# automa_o_granja.net
KiCad netlist of a schematic drawn in EAGLE
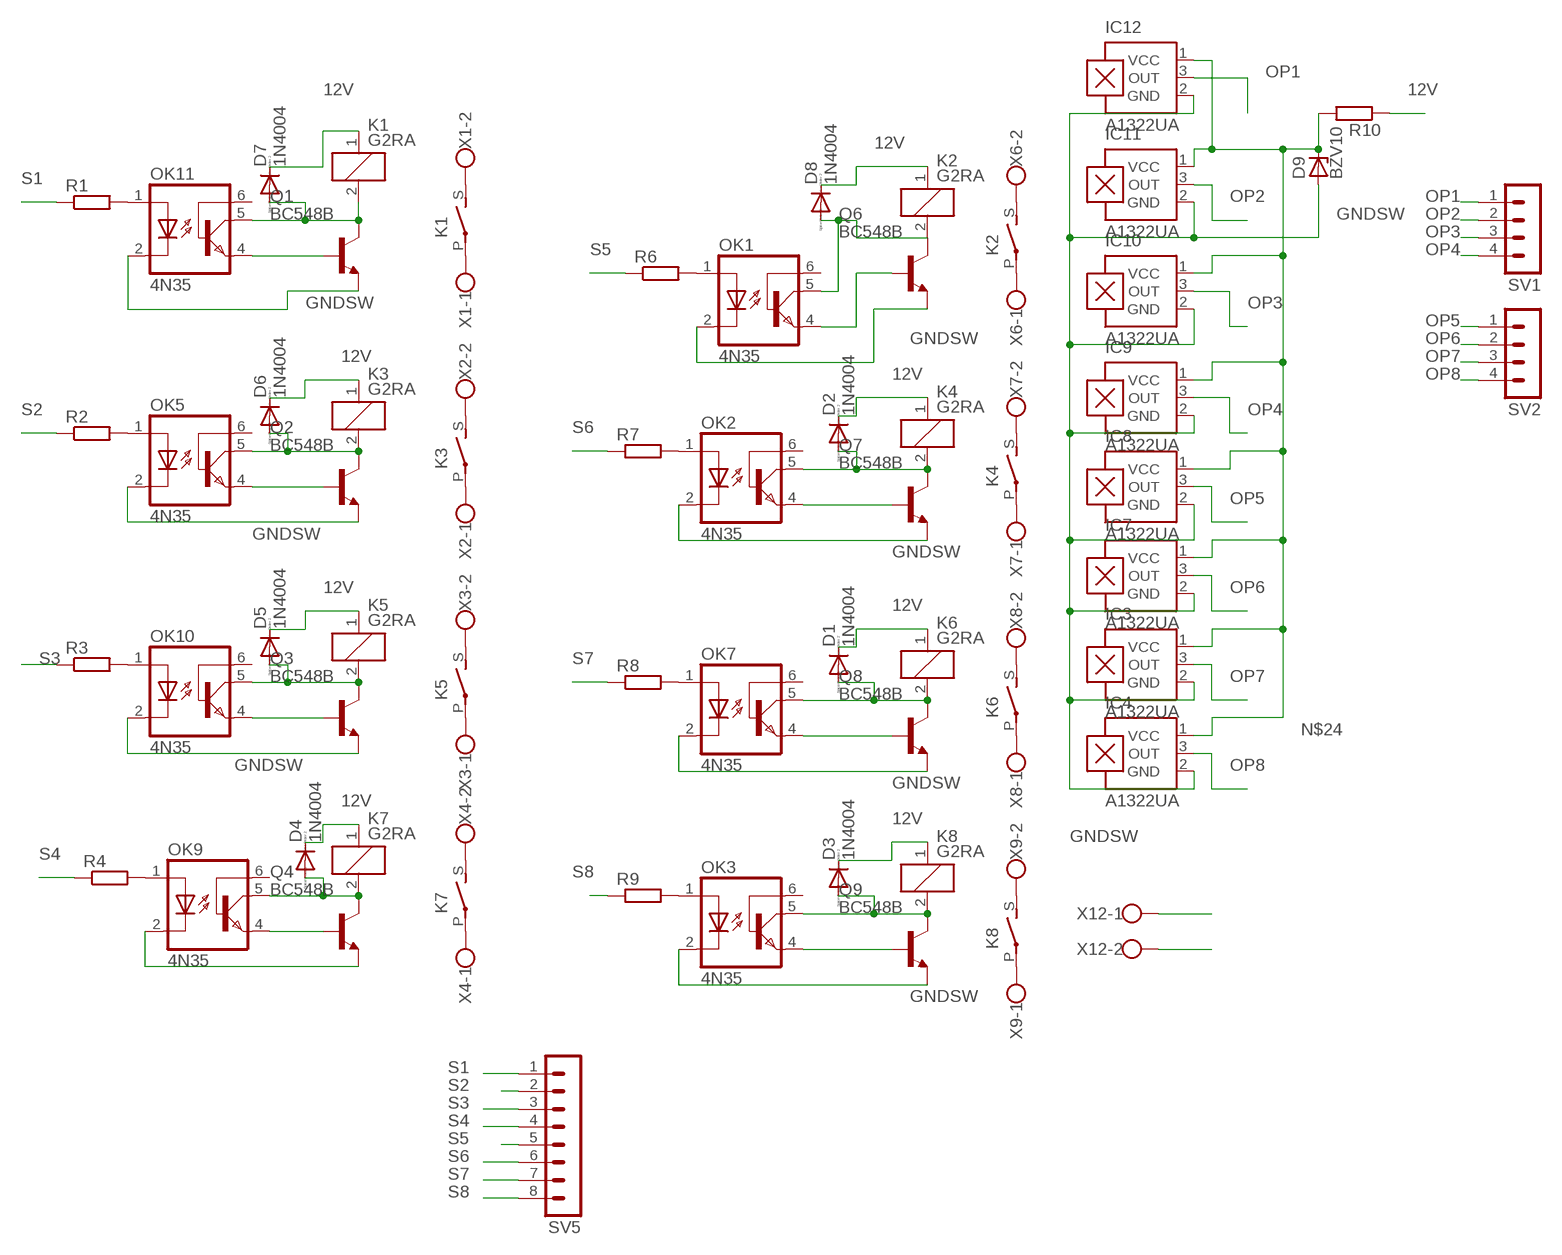
[diagram p0: schematic, sheet 1]

(export (version "E")
  (design (tool "Eeschema 10.0.6"))
  (components
    (comp (ref "D1")
      (value "1N4004")
      (footprint "eagle-import:DO41-10")
      (libsource (lib "eagle-import") (part "1N4004"))
    )
    (comp (ref "D2")
      (value "1N4004")
      (footprint "eagle-import:DO41-10")
      (libsource (lib "eagle-import") (part "1N4004"))
    )
    (comp (ref "D3")
      (value "1N4004")
      (footprint "eagle-import:DO41-10")
      (libsource (lib "eagle-import") (part "1N4004"))
    )
    (comp (ref "D4")
      (value "1N4004")
      (footprint "eagle-import:DO41-10")
      (libsource (lib "eagle-import") (part "1N4004"))
    )
    (comp (ref "D5")
      (value "1N4004")
      (footprint "eagle-import:DO41-10")
      (libsource (lib "eagle-import") (part "1N4004"))
    )
    (comp (ref "D6")
      (value "1N4004")
      (footprint "eagle-import:DO41-10")
      (libsource (lib "eagle-import") (part "1N4004"))
    )
    (comp (ref "D7")
      (value "1N4004")
      (footprint "eagle-import:DO41-10")
      (libsource (lib "eagle-import") (part "1N4004"))
    )
    (comp (ref "D8")
      (value "1N4004")
      (footprint "eagle-import:DO41-10")
      (libsource (lib "eagle-import") (part "1N4004"))
    )
    (comp (ref "D9")
      (value "BZV10")
      (footprint "eagle-import:DO34Z7")
      (libsource (lib "eagle-import") (part "BZV10"))
    )
    (comp (ref "IC3")
      (value "A1322UA")
      (footprint "eagle-import:SIP3-UA")
      (fields (field (name "MF") "ALLEGRO MICROSYSTEMS, INC.") (field (name "MPN") "A1322LUA-T"))
      (libsource (lib "eagle-import") (part "A13?UA22"))
    )
    (comp (ref "IC4")
      (value "A1322UA")
      (footprint "eagle-import:SIP3-UA")
      (fields (field (name "MF") "ALLEGRO MICROSYSTEMS, INC.") (field (name "MPN") "A1322LUA-T"))
      (libsource (lib "eagle-import") (part "A13?UA22"))
    )
    (comp (ref "IC7")
      (value "A1322UA")
      (footprint "eagle-import:SIP3-UA")
      (fields (field (name "MF") "ALLEGRO MICROSYSTEMS, INC.") (field (name "MPN") "A1322LUA-T"))
      (libsource (lib "eagle-import") (part "A13?UA22"))
    )
    (comp (ref "IC8")
      (value "A1322UA")
      (footprint "eagle-import:SIP3-UA")
      (fields (field (name "MF") "ALLEGRO MICROSYSTEMS, INC.") (field (name "MPN") "A1322LUA-T"))
      (libsource (lib "eagle-import") (part "A13?UA22"))
    )
    (comp (ref "IC9")
      (value "A1322UA")
      (footprint "eagle-import:SIP3-UA")
      (fields (field (name "MF") "ALLEGRO MICROSYSTEMS, INC.") (field (name "MPN") "A1322LUA-T"))
      (libsource (lib "eagle-import") (part "A13?UA22"))
    )
    (comp (ref "IC10")
      (value "A1322UA")
      (footprint "eagle-import:SIP3-UA")
      (fields (field (name "MF") "ALLEGRO MICROSYSTEMS, INC.") (field (name "MPN") "A1322LUA-T"))
      (libsource (lib "eagle-import") (part "A13?UA22"))
    )
    (comp (ref "IC11")
      (value "A1322UA")
      (footprint "eagle-import:SIP3-UA")
      (fields (field (name "MF") "ALLEGRO MICROSYSTEMS, INC.") (field (name "MPN") "A1322LUA-T"))
      (libsource (lib "eagle-import") (part "A13?UA22"))
    )
    (comp (ref "IC12")
      (value "A1322UA")
      (footprint "eagle-import:SIP3-UA")
      (fields (field (name "MF") "ALLEGRO MICROSYSTEMS, INC.") (field (name "MPN") "A1322LUA-T"))
      (libsource (lib "eagle-import") (part "A13?UA22"))
    )
    (comp (ref "K1")
      (value "G2RA")
      (footprint "eagle-import:G2RA")
      (libsource (lib "eagle-import") (part "G2RA"))
    )
    (comp (ref "K2")
      (value "G2RA")
      (footprint "eagle-import:G2RA")
      (libsource (lib "eagle-import") (part "G2RA"))
    )
    (comp (ref "K3")
      (value "G2RA")
      (footprint "eagle-import:G2RA")
      (libsource (lib "eagle-import") (part "G2RA"))
    )
    (comp (ref "K4")
      (value "G2RA")
      (footprint "eagle-import:G2RA")
      (libsource (lib "eagle-import") (part "G2RA"))
    )
    (comp (ref "K5")
      (value "G2RA")
      (footprint "eagle-import:G2RA")
      (libsource (lib "eagle-import") (part "G2RA"))
    )
    (comp (ref "K6")
      (value "G2RA")
      (footprint "eagle-import:G2RA")
      (libsource (lib "eagle-import") (part "G2RA"))
    )
    (comp (ref "K7")
      (value "G2RA")
      (footprint "eagle-import:G2RA")
      (libsource (lib "eagle-import") (part "G2RA"))
    )
    (comp (ref "K8")
      (value "G2RA")
      (footprint "eagle-import:G2RA")
      (libsource (lib "eagle-import") (part "G2RA"))
    )
    (comp (ref "OK1")
      (value "4N35")
      (footprint "eagle-import:DIL06")
      (fields (field (name "MF") "FAIRCHILD SEMICONDUCTOR"))
      (libsource (lib "eagle-import") (part "4N35"))
    )
    (comp (ref "OK2")
      (value "4N35")
      (footprint "eagle-import:DIL06")
      (fields (field (name "MF") "FAIRCHILD SEMICONDUCTOR"))
      (libsource (lib "eagle-import") (part "4N35"))
    )
    (comp (ref "OK3")
      (value "4N35")
      (footprint "eagle-import:DIL06")
      (fields (field (name "MF") "FAIRCHILD SEMICONDUCTOR"))
      (libsource (lib "eagle-import") (part "4N35"))
    )
    (comp (ref "OK5")
      (value "4N35")
      (footprint "eagle-import:DIL06")
      (fields (field (name "MF") "FAIRCHILD SEMICONDUCTOR"))
      (libsource (lib "eagle-import") (part "4N35"))
    )
    (comp (ref "OK7")
      (value "4N35")
      (footprint "eagle-import:DIL06")
      (fields (field (name "MF") "FAIRCHILD SEMICONDUCTOR"))
      (libsource (lib "eagle-import") (part "4N35"))
    )
    (comp (ref "OK9")
      (value "4N35")
      (footprint "eagle-import:DIL06")
      (fields (field (name "MF") "FAIRCHILD SEMICONDUCTOR"))
      (libsource (lib "eagle-import") (part "4N35"))
    )
    (comp (ref "OK10")
      (value "4N35")
      (footprint "eagle-import:DIL06")
      (fields (field (name "MF") "FAIRCHILD SEMICONDUCTOR"))
      (libsource (lib "eagle-import") (part "4N35"))
    )
    (comp (ref "OK11")
      (value "4N35")
      (footprint "eagle-import:DIL06")
      (fields (field (name "MF") "FAIRCHILD SEMICONDUCTOR"))
      (libsource (lib "eagle-import") (part "4N35"))
    )
    (comp (ref "Q1")
      (value "BC548B")
      (footprint "eagle-import:TO92-EBC")
      (libsource (lib "eagle-import") (part "BC548B"))
    )
    (comp (ref "Q2")
      (value "BC548B")
      (footprint "eagle-import:TO92-EBC")
      (libsource (lib "eagle-import") (part "BC548B"))
    )
    (comp (ref "Q3")
      (value "BC548B")
      (footprint "eagle-import:TO92-EBC")
      (libsource (lib "eagle-import") (part "BC548B"))
    )
    (comp (ref "Q4")
      (value "BC548B")
      (footprint "eagle-import:TO92-EBC")
      (libsource (lib "eagle-import") (part "BC548B"))
    )
    (comp (ref "Q6")
      (value "BC548B")
      (footprint "eagle-import:TO92-EBC")
      (libsource (lib "eagle-import") (part "BC548B"))
    )
    (comp (ref "Q7")
      (value "BC548B")
      (footprint "eagle-import:TO92-EBC")
      (libsource (lib "eagle-import") (part "BC548B"))
    )
    (comp (ref "Q8")
      (value "BC548B")
      (footprint "eagle-import:TO92-EBC")
      (libsource (lib "eagle-import") (part "BC548B"))
    )
    (comp (ref "Q9")
      (value "BC548B")
      (footprint "eagle-import:TO92-EBC")
      (libsource (lib "eagle-import") (part "BC548B"))
    )
    (comp (ref "R1")
      (value "R-EU_0207/7")
      (footprint "eagle-import:0207_7")
      (libsource (lib "eagle-import") (part "R-EU_0207/7"))
    )
    (comp (ref "R2")
      (value "R-EU_0207/7")
      (footprint "eagle-import:0207_7")
      (libsource (lib "eagle-import") (part "R-EU_0207/7"))
    )
    (comp (ref "R3")
      (value "R-EU_0207/7")
      (footprint "eagle-import:0207_7")
      (libsource (lib "eagle-import") (part "R-EU_0207/7"))
    )
    (comp (ref "R4")
      (value "R-EU_0207/7")
      (footprint "eagle-import:0207_7")
      (libsource (lib "eagle-import") (part "R-EU_0207/7"))
    )
    (comp (ref "R6")
      (value "R-EU_0207/7")
      (footprint "eagle-import:0207_7")
      (libsource (lib "eagle-import") (part "R-EU_0207/7"))
    )
    (comp (ref "R7")
      (value "R-EU_0207/7")
      (footprint "eagle-import:0207_7")
      (libsource (lib "eagle-import") (part "R-EU_0207/7"))
    )
    (comp (ref "R8")
      (value "R-EU_0207/7")
      (footprint "eagle-import:0207_7")
      (libsource (lib "eagle-import") (part "R-EU_0207/7"))
    )
    (comp (ref "R9")
      (value "R-EU_0207/7")
      (footprint "eagle-import:0207_7")
      (libsource (lib "eagle-import") (part "R-EU_0207/7"))
    )
    (comp (ref "R10")
      (value "R-EU_0207/7")
      (footprint "eagle-import:0207_7")
      (libsource (lib "eagle-import") (part "R-EU_0207/7"))
    )
    (comp (ref "SV1")
      (value "MA04-1")
      (footprint "eagle-import:MA04-1")
      (libsource (lib "eagle-import") (part "MA04-1"))
    )
    (comp (ref "SV2")
      (value "MA04-1")
      (footprint "eagle-import:MA04-1")
      (libsource (lib "eagle-import") (part "MA04-1"))
    )
    (comp (ref "SV5")
      (value "MA08-1")
      (footprint "eagle-import:MA08-1")
      (libsource (lib "eagle-import") (part "MA08-1"))
    )
    (comp (ref "X1")
      (value "W237-102")
      (footprint "eagle-import:W237-102")
      (fields (field (name "MPN") "237-102"))
      (libsource (lib "eagle-import") (part "W237-102"))
    )
    (comp (ref "X2")
      (value "W237-102")
      (footprint "eagle-import:W237-102")
      (fields (field (name "MPN") "237-102"))
      (libsource (lib "eagle-import") (part "W237-102"))
    )
    (comp (ref "X3")
      (value "W237-102")
      (footprint "eagle-import:W237-102")
      (fields (field (name "MPN") "237-102"))
      (libsource (lib "eagle-import") (part "W237-102"))
    )
    (comp (ref "X4")
      (value "W237-102")
      (footprint "eagle-import:W237-102")
      (fields (field (name "MPN") "237-102"))
      (libsource (lib "eagle-import") (part "W237-102"))
    )
    (comp (ref "X6")
      (value "W237-102")
      (footprint "eagle-import:W237-102")
      (fields (field (name "MPN") "237-102"))
      (libsource (lib "eagle-import") (part "W237-102"))
    )
    (comp (ref "X7")
      (value "W237-102")
      (footprint "eagle-import:W237-102")
      (fields (field (name "MPN") "237-102"))
      (libsource (lib "eagle-import") (part "W237-102"))
    )
    (comp (ref "X8")
      (value "W237-102")
      (footprint "eagle-import:W237-102")
      (fields (field (name "MPN") "237-102"))
      (libsource (lib "eagle-import") (part "W237-102"))
    )
    (comp (ref "X9")
      (value "W237-102")
      (footprint "eagle-import:W237-102")
      (fields (field (name "MPN") "237-102"))
      (libsource (lib "eagle-import") (part "W237-102"))
    )
    (comp (ref "X12")
      (value "W237-102")
      (footprint "eagle-import:W237-102")
      (fields (field (name "MPN") "237-102"))
      (libsource (lib "eagle-import") (part "W237-102"))
    )
  )
  (nets
    (net (code "1") (name "/12V") (class "Default")
      (node (ref "D1") (pin "C") (pinfunction "C_C") (pintype "passive"))
      (node (ref "D2") (pin "C") (pinfunction "C_C") (pintype "passive"))
      (node (ref "D3") (pin "C") (pinfunction "C_C") (pintype "passive"))
      (node (ref "D4") (pin "C") (pinfunction "C_C") (pintype "passive"))
      (node (ref "D5") (pin "C") (pinfunction "C_C") (pintype "passive"))
      (node (ref "D6") (pin "C") (pinfunction "C_C") (pintype "passive"))
      (node (ref "D7") (pin "C") (pinfunction "C_C") (pintype "passive"))
      (node (ref "D8") (pin "C") (pinfunction "C_C") (pintype "passive"))
      (node (ref "K1") (pin "1") (pinfunction "1_1") (pintype "passive"))
      (node (ref "K2") (pin "1") (pinfunction "1_1") (pintype "passive"))
      (node (ref "K3") (pin "1") (pinfunction "1_1") (pintype "passive"))
      (node (ref "K4") (pin "1") (pinfunction "1_1") (pintype "passive"))
      (node (ref "K5") (pin "1") (pinfunction "1_1") (pintype "passive"))
      (node (ref "K6") (pin "1") (pinfunction "1_1") (pintype "passive"))
      (node (ref "K7") (pin "1") (pinfunction "1_1") (pintype "passive"))
      (node (ref "K8") (pin "1") (pinfunction "1_1") (pintype "passive"))
      (node (ref "R10") (pin "1") (pinfunction "1_1") (pintype "passive"))
      (node (ref "X12") (pin "1") (pinfunction "KL_1") (pintype "passive"))
    )
    (net (code "2") (name "/GNDSW") (class "Default")
      (node (ref "D9") (pin "A") (pinfunction "A_A") (pintype "passive"))
      (node (ref "IC10") (pin "2") (pinfunction "GND_2") (pintype "power_in"))
      (node (ref "IC11") (pin "2") (pinfunction "GND_2") (pintype "power_in"))
      (node (ref "IC12") (pin "2") (pinfunction "GND_2") (pintype "power_in"))
      (node (ref "IC3") (pin "2") (pinfunction "GND_2") (pintype "power_in"))
      (node (ref "IC4") (pin "2") (pinfunction "GND_2") (pintype "power_in"))
      (node (ref "IC7") (pin "2") (pinfunction "GND_2") (pintype "power_in"))
      (node (ref "IC8") (pin "2") (pinfunction "GND_2") (pintype "power_in"))
      (node (ref "IC9") (pin "2") (pinfunction "GND_2") (pintype "power_in"))
      (node (ref "OK1") (pin "2") (pinfunction "C_2") (pintype "passive"))
      (node (ref "OK10") (pin "2") (pinfunction "C_2") (pintype "passive"))
      (node (ref "OK11") (pin "2") (pinfunction "C_2") (pintype "passive"))
      (node (ref "OK2") (pin "2") (pinfunction "C_2") (pintype "passive"))
      (node (ref "OK3") (pin "2") (pinfunction "C_2") (pintype "passive"))
      (node (ref "OK5") (pin "2") (pinfunction "C_2") (pintype "passive"))
      (node (ref "OK7") (pin "2") (pinfunction "C_2") (pintype "passive"))
      (node (ref "OK9") (pin "2") (pinfunction "C_2") (pintype "passive"))
      (node (ref "Q1") (pin "E") (pinfunction "E_E") (pintype "passive"))
      (node (ref "Q2") (pin "E") (pinfunction "E_E") (pintype "passive"))
      (node (ref "Q3") (pin "E") (pinfunction "E_E") (pintype "passive"))
      (node (ref "Q4") (pin "E") (pinfunction "E_E") (pintype "passive"))
      (node (ref "Q6") (pin "E") (pinfunction "E_E") (pintype "passive"))
      (node (ref "Q7") (pin "E") (pinfunction "E_E") (pintype "passive"))
      (node (ref "Q8") (pin "E") (pinfunction "E_E") (pintype "passive"))
      (node (ref "Q9") (pin "E") (pinfunction "E_E") (pintype "passive"))
      (node (ref "X12") (pin "2") (pinfunction "KL_2") (pintype "passive"))
    )
    (net (code "3") (name "/N$24") (class "Default")
      (node (ref "D9") (pin "C") (pinfunction "C_C") (pintype "passive"))
      (node (ref "IC10") (pin "1") (pinfunction "VCC_1") (pintype "power_in"))
      (node (ref "IC11") (pin "1") (pinfunction "VCC_1") (pintype "power_in"))
      (node (ref "IC12") (pin "1") (pinfunction "VCC_1") (pintype "power_in"))
      (node (ref "IC3") (pin "1") (pinfunction "VCC_1") (pintype "power_in"))
      (node (ref "IC4") (pin "1") (pinfunction "VCC_1") (pintype "power_in"))
      (node (ref "IC7") (pin "1") (pinfunction "VCC_1") (pintype "power_in"))
      (node (ref "IC8") (pin "1") (pinfunction "VCC_1") (pintype "power_in"))
      (node (ref "IC9") (pin "1") (pinfunction "VCC_1") (pintype "power_in"))
      (node (ref "R10") (pin "2") (pinfunction "2_2") (pintype "passive"))
    )
    (net (code "4") (name "/OP1") (class "Default")
      (node (ref "IC12") (pin "3") (pinfunction "OUT_3") (pintype "output"))
      (node (ref "SV1") (pin "1") (pinfunction "1_1") (pintype "passive"))
    )
    (net (code "5") (name "/OP2") (class "Default")
      (node (ref "IC11") (pin "3") (pinfunction "OUT_3") (pintype "output"))
      (node (ref "SV1") (pin "2") (pinfunction "2_2") (pintype "passive"))
    )
    (net (code "6") (name "/OP3") (class "Default")
      (node (ref "IC10") (pin "3") (pinfunction "OUT_3") (pintype "output"))
      (node (ref "SV1") (pin "3") (pinfunction "3_3") (pintype "passive"))
    )
    (net (code "7") (name "/OP4") (class "Default")
      (node (ref "IC9") (pin "3") (pinfunction "OUT_3") (pintype "output"))
      (node (ref "SV1") (pin "4") (pinfunction "4_4") (pintype "passive"))
    )
    (net (code "8") (name "/OP5") (class "Default")
      (node (ref "IC8") (pin "3") (pinfunction "OUT_3") (pintype "output"))
      (node (ref "SV2") (pin "1") (pinfunction "1_1") (pintype "passive"))
    )
    (net (code "9") (name "/OP6") (class "Default")
      (node (ref "IC7") (pin "3") (pinfunction "OUT_3") (pintype "output"))
      (node (ref "SV2") (pin "2") (pinfunction "2_2") (pintype "passive"))
    )
    (net (code "10") (name "/OP7") (class "Default")
      (node (ref "IC3") (pin "3") (pinfunction "OUT_3") (pintype "output"))
      (node (ref "SV2") (pin "3") (pinfunction "3_3") (pintype "passive"))
    )
    (net (code "11") (name "/OP8") (class "Default")
      (node (ref "IC4") (pin "3") (pinfunction "OUT_3") (pintype "output"))
      (node (ref "SV2") (pin "4") (pinfunction "4_4") (pintype "passive"))
    )
    (net (code "12") (name "/S1") (class "Default")
      (node (ref "R1") (pin "1") (pinfunction "1_1") (pintype "passive"))
      (node (ref "SV5") (pin "1") (pinfunction "1_1") (pintype "passive"))
    )
    (net (code "13") (name "/S2") (class "Default")
      (node (ref "R2") (pin "1") (pinfunction "1_1") (pintype "passive"))
      (node (ref "SV5") (pin "2") (pinfunction "2_2") (pintype "passive"))
    )
    (net (code "14") (name "/S3") (class "Default")
      (node (ref "R3") (pin "1") (pinfunction "1_1") (pintype "passive"))
      (node (ref "SV5") (pin "3") (pinfunction "3_3") (pintype "passive"))
    )
    (net (code "15") (name "/S4") (class "Default")
      (node (ref "R4") (pin "1") (pinfunction "1_1") (pintype "passive"))
      (node (ref "SV5") (pin "4") (pinfunction "4_4") (pintype "passive"))
    )
    (net (code "16") (name "/S5") (class "Default")
      (node (ref "R6") (pin "1") (pinfunction "1_1") (pintype "passive"))
      (node (ref "SV5") (pin "5") (pinfunction "5_5") (pintype "passive"))
    )
    (net (code "17") (name "/S6") (class "Default")
      (node (ref "R7") (pin "1") (pinfunction "1_1") (pintype "passive"))
      (node (ref "SV5") (pin "6") (pinfunction "6_6") (pintype "passive"))
    )
    (net (code "18") (name "/S7") (class "Default")
      (node (ref "R8") (pin "1") (pinfunction "1_1") (pintype "passive"))
      (node (ref "SV5") (pin "7") (pinfunction "7_7") (pintype "passive"))
    )
    (net (code "19") (name "/S8") (class "Default")
      (node (ref "R9") (pin "1") (pinfunction "1_1") (pintype "passive"))
      (node (ref "SV5") (pin "8") (pinfunction "8_8") (pintype "passive"))
    )
    (net (code "20") (name "Net-(OK1-A)") (class "Default")
      (node (ref "OK1") (pin "1") (pinfunction "A_1") (pintype "passive"))
      (node (ref "R6") (pin "2") (pinfunction "2_2") (pintype "passive"))
    )
    (net (code "21") (name "Net-(OK1-COL)") (class "Default")
      (node (ref "D8") (pin "A") (pinfunction "A_A") (pintype "passive"))
      (node (ref "K2") (pin "2") (pinfunction "2_2") (pintype "passive"))
      (node (ref "OK1") (pin "5") (pinfunction "COL_5") (pintype "passive"))
      (node (ref "Q6") (pin "C") (pinfunction "C_C") (pintype "passive"))
    )
    (net (code "22") (name "Net-(OK1-EMI)") (class "Default")
      (node (ref "OK1") (pin "4") (pinfunction "EMI_4") (pintype "passive"))
      (node (ref "Q6") (pin "B") (pinfunction "B_B") (pintype "passive"))
    )
    (net (code "23") (name "Net-(OK2-A)") (class "Default")
      (node (ref "OK2") (pin "1") (pinfunction "A_1") (pintype "passive"))
      (node (ref "R7") (pin "2") (pinfunction "2_2") (pintype "passive"))
    )
    (net (code "24") (name "Net-(OK2-COL)") (class "Default")
      (node (ref "D2") (pin "A") (pinfunction "A_A") (pintype "passive"))
      (node (ref "K4") (pin "2") (pinfunction "2_2") (pintype "passive"))
      (node (ref "OK2") (pin "5") (pinfunction "COL_5") (pintype "passive"))
      (node (ref "Q7") (pin "C") (pinfunction "C_C") (pintype "passive"))
    )
    (net (code "25") (name "Net-(OK2-EMI)") (class "Default")
      (node (ref "OK2") (pin "4") (pinfunction "EMI_4") (pintype "passive"))
      (node (ref "Q7") (pin "B") (pinfunction "B_B") (pintype "passive"))
    )
    (net (code "26") (name "Net-(OK3-A)") (class "Default")
      (node (ref "OK3") (pin "1") (pinfunction "A_1") (pintype "passive"))
      (node (ref "R9") (pin "2") (pinfunction "2_2") (pintype "passive"))
    )
    (net (code "27") (name "Net-(OK3-COL)") (class "Default")
      (node (ref "D3") (pin "A") (pinfunction "A_A") (pintype "passive"))
      (node (ref "K8") (pin "2") (pinfunction "2_2") (pintype "passive"))
      (node (ref "OK3") (pin "5") (pinfunction "COL_5") (pintype "passive"))
      (node (ref "Q9") (pin "C") (pinfunction "C_C") (pintype "passive"))
    )
    (net (code "28") (name "Net-(OK3-EMI)") (class "Default")
      (node (ref "OK3") (pin "4") (pinfunction "EMI_4") (pintype "passive"))
      (node (ref "Q9") (pin "B") (pinfunction "B_B") (pintype "passive"))
    )
    (net (code "29") (name "Net-(OK5-A)") (class "Default")
      (node (ref "OK5") (pin "1") (pinfunction "A_1") (pintype "passive"))
      (node (ref "R2") (pin "2") (pinfunction "2_2") (pintype "passive"))
    )
    (net (code "30") (name "Net-(OK5-COL)") (class "Default")
      (node (ref "D6") (pin "A") (pinfunction "A_A") (pintype "passive"))
      (node (ref "K3") (pin "2") (pinfunction "2_2") (pintype "passive"))
      (node (ref "OK5") (pin "5") (pinfunction "COL_5") (pintype "passive"))
      (node (ref "Q2") (pin "C") (pinfunction "C_C") (pintype "passive"))
    )
    (net (code "31") (name "Net-(OK5-EMI)") (class "Default")
      (node (ref "OK5") (pin "4") (pinfunction "EMI_4") (pintype "passive"))
      (node (ref "Q2") (pin "B") (pinfunction "B_B") (pintype "passive"))
    )
    (net (code "32") (name "Net-(OK7-A)") (class "Default")
      (node (ref "OK7") (pin "1") (pinfunction "A_1") (pintype "passive"))
      (node (ref "R8") (pin "2") (pinfunction "2_2") (pintype "passive"))
    )
    (net (code "33") (name "Net-(OK7-COL)") (class "Default")
      (node (ref "D1") (pin "A") (pinfunction "A_A") (pintype "passive"))
      (node (ref "K6") (pin "2") (pinfunction "2_2") (pintype "passive"))
      (node (ref "OK7") (pin "5") (pinfunction "COL_5") (pintype "passive"))
      (node (ref "Q8") (pin "C") (pinfunction "C_C") (pintype "passive"))
    )
    (net (code "34") (name "Net-(OK7-EMI)") (class "Default")
      (node (ref "OK7") (pin "4") (pinfunction "EMI_4") (pintype "passive"))
      (node (ref "Q8") (pin "B") (pinfunction "B_B") (pintype "passive"))
    )
    (net (code "35") (name "Net-(OK9-A)") (class "Default")
      (node (ref "OK9") (pin "1") (pinfunction "A_1") (pintype "passive"))
      (node (ref "R4") (pin "2") (pinfunction "2_2") (pintype "passive"))
    )
    (net (code "36") (name "Net-(OK9-COL)") (class "Default")
      (node (ref "D4") (pin "A") (pinfunction "A_A") (pintype "passive"))
      (node (ref "K7") (pin "2") (pinfunction "2_2") (pintype "passive"))
      (node (ref "OK9") (pin "5") (pinfunction "COL_5") (pintype "passive"))
      (node (ref "Q4") (pin "C") (pinfunction "C_C") (pintype "passive"))
    )
    (net (code "37") (name "Net-(OK9-EMI)") (class "Default")
      (node (ref "OK9") (pin "4") (pinfunction "EMI_4") (pintype "passive"))
      (node (ref "Q4") (pin "B") (pinfunction "B_B") (pintype "passive"))
    )
    (net (code "38") (name "Net-(OK10-A)") (class "Default")
      (node (ref "OK10") (pin "1") (pinfunction "A_1") (pintype "passive"))
      (node (ref "R3") (pin "2") (pinfunction "2_2") (pintype "passive"))
    )
    (net (code "39") (name "Net-(OK10-COL)") (class "Default")
      (node (ref "D5") (pin "A") (pinfunction "A_A") (pintype "passive"))
      (node (ref "K5") (pin "2") (pinfunction "2_2") (pintype "passive"))
      (node (ref "OK10") (pin "5") (pinfunction "COL_5") (pintype "passive"))
      (node (ref "Q3") (pin "C") (pinfunction "C_C") (pintype "passive"))
    )
    (net (code "40") (name "Net-(OK10-EMI)") (class "Default")
      (node (ref "OK10") (pin "4") (pinfunction "EMI_4") (pintype "passive"))
      (node (ref "Q3") (pin "B") (pinfunction "B_B") (pintype "passive"))
    )
    (net (code "41") (name "Net-(OK11-A)") (class "Default")
      (node (ref "OK11") (pin "1") (pinfunction "A_1") (pintype "passive"))
      (node (ref "R1") (pin "2") (pinfunction "2_2") (pintype "passive"))
    )
    (net (code "42") (name "Net-(OK11-COL)") (class "Default")
      (node (ref "D7") (pin "A") (pinfunction "A_A") (pintype "passive"))
      (node (ref "K1") (pin "2") (pinfunction "2_2") (pintype "passive"))
      (node (ref "OK11") (pin "5") (pinfunction "COL_5") (pintype "passive"))
      (node (ref "Q1") (pin "C") (pinfunction "C_C") (pintype "passive"))
    )
    (net (code "43") (name "Net-(OK11-EMI)") (class "Default")
      (node (ref "OK11") (pin "4") (pinfunction "EMI_4") (pintype "passive"))
      (node (ref "Q1") (pin "B") (pinfunction "B_B") (pintype "passive"))
    )
    (net (code "44") (name "Net-(X1A-KL)") (class "Default")
      (node (ref "K1") (pin "P") (pinfunction "P_P") (pintype "passive"))
      (node (ref "X1") (pin "1") (pinfunction "KL_1") (pintype "passive"))
    )
    (net (code "45") (name "Net-(X1B-KL)") (class "Default")
      (node (ref "K1") (pin "S") (pinfunction "S_S") (pintype "passive"))
      (node (ref "X1") (pin "2") (pinfunction "KL_2") (pintype "passive"))
    )
    (net (code "46") (name "Net-(X2A-KL)") (class "Default")
      (node (ref "K3") (pin "P") (pinfunction "P_P") (pintype "passive"))
      (node (ref "X2") (pin "1") (pinfunction "KL_1") (pintype "passive"))
    )
    (net (code "47") (name "Net-(X2B-KL)") (class "Default")
      (node (ref "K3") (pin "S") (pinfunction "S_S") (pintype "passive"))
      (node (ref "X2") (pin "2") (pinfunction "KL_2") (pintype "passive"))
    )
    (net (code "48") (name "Net-(X3A-KL)") (class "Default")
      (node (ref "K5") (pin "P") (pinfunction "P_P") (pintype "passive"))
      (node (ref "X3") (pin "1") (pinfunction "KL_1") (pintype "passive"))
    )
    (net (code "49") (name "Net-(X3B-KL)") (class "Default")
      (node (ref "K5") (pin "S") (pinfunction "S_S") (pintype "passive"))
      (node (ref "X3") (pin "2") (pinfunction "KL_2") (pintype "passive"))
    )
    (net (code "50") (name "Net-(X4A-KL)") (class "Default")
      (node (ref "K7") (pin "P") (pinfunction "P_P") (pintype "passive"))
      (node (ref "X4") (pin "1") (pinfunction "KL_1") (pintype "passive"))
    )
    (net (code "51") (name "Net-(X4B-KL)") (class "Default")
      (node (ref "K7") (pin "S") (pinfunction "S_S") (pintype "passive"))
      (node (ref "X4") (pin "2") (pinfunction "KL_2") (pintype "passive"))
    )
    (net (code "52") (name "Net-(X6A-KL)") (class "Default")
      (node (ref "K2") (pin "P") (pinfunction "P_P") (pintype "passive"))
      (node (ref "X6") (pin "1") (pinfunction "KL_1") (pintype "passive"))
    )
    (net (code "53") (name "Net-(X6B-KL)") (class "Default")
      (node (ref "K2") (pin "S") (pinfunction "S_S") (pintype "passive"))
      (node (ref "X6") (pin "2") (pinfunction "KL_2") (pintype "passive"))
    )
    (net (code "54") (name "Net-(X7A-KL)") (class "Default")
      (node (ref "K4") (pin "P") (pinfunction "P_P") (pintype "passive"))
      (node (ref "X7") (pin "1") (pinfunction "KL_1") (pintype "passive"))
    )
    (net (code "55") (name "Net-(X7B-KL)") (class "Default")
      (node (ref "K4") (pin "S") (pinfunction "S_S") (pintype "passive"))
      (node (ref "X7") (pin "2") (pinfunction "KL_2") (pintype "passive"))
    )
    (net (code "56") (name "Net-(X8A-KL)") (class "Default")
      (node (ref "K6") (pin "P") (pinfunction "P_P") (pintype "passive"))
      (node (ref "X8") (pin "1") (pinfunction "KL_1") (pintype "passive"))
    )
    (net (code "57") (name "Net-(X8B-KL)") (class "Default")
      (node (ref "K6") (pin "S") (pinfunction "S_S") (pintype "passive"))
      (node (ref "X8") (pin "2") (pinfunction "KL_2") (pintype "passive"))
    )
    (net (code "58") (name "Net-(X9A-KL)") (class "Default")
      (node (ref "K8") (pin "P") (pinfunction "P_P") (pintype "passive"))
      (node (ref "X9") (pin "1") (pinfunction "KL_1") (pintype "passive"))
    )
    (net (code "59") (name "Net-(X9B-KL)") (class "Default")
      (node (ref "K8") (pin "S") (pinfunction "S_S") (pintype "passive"))
      (node (ref "X9") (pin "2") (pinfunction "KL_2") (pintype "passive"))
    )
    (net (code "60") (name "unconnected-(OK1-BAS-Pad6)") (class "Default")
      (node (ref "OK1") (pin "6") (pinfunction "BAS_6") (pintype "passive"))
    )
    (net (code "61") (name "unconnected-(OK2-BAS-Pad6)") (class "Default")
      (node (ref "OK2") (pin "6") (pinfunction "BAS_6") (pintype "passive"))
    )
    (net (code "62") (name "unconnected-(OK3-BAS-Pad6)") (class "Default")
      (node (ref "OK3") (pin "6") (pinfunction "BAS_6") (pintype "passive"))
    )
    (net (code "63") (name "unconnected-(OK5-BAS-Pad6)") (class "Default")
      (node (ref "OK5") (pin "6") (pinfunction "BAS_6") (pintype "passive"))
    )
    (net (code "64") (name "unconnected-(OK7-BAS-Pad6)") (class "Default")
      (node (ref "OK7") (pin "6") (pinfunction "BAS_6") (pintype "passive"))
    )
    (net (code "65") (name "unconnected-(OK9-BAS-Pad6)") (class "Default")
      (node (ref "OK9") (pin "6") (pinfunction "BAS_6") (pintype "passive"))
    )
    (net (code "66") (name "unconnected-(OK10-BAS-Pad6)") (class "Default")
      (node (ref "OK10") (pin "6") (pinfunction "BAS_6") (pintype "passive"))
    )
    (net (code "67") (name "unconnected-(OK11-BAS-Pad6)") (class "Default")
      (node (ref "OK11") (pin "6") (pinfunction "BAS_6") (pintype "passive"))
    )
  )
)
